# DAPule-LPC11U35-v1_2_0.net
KiCad netlist of a schematic drawn in EAGLE
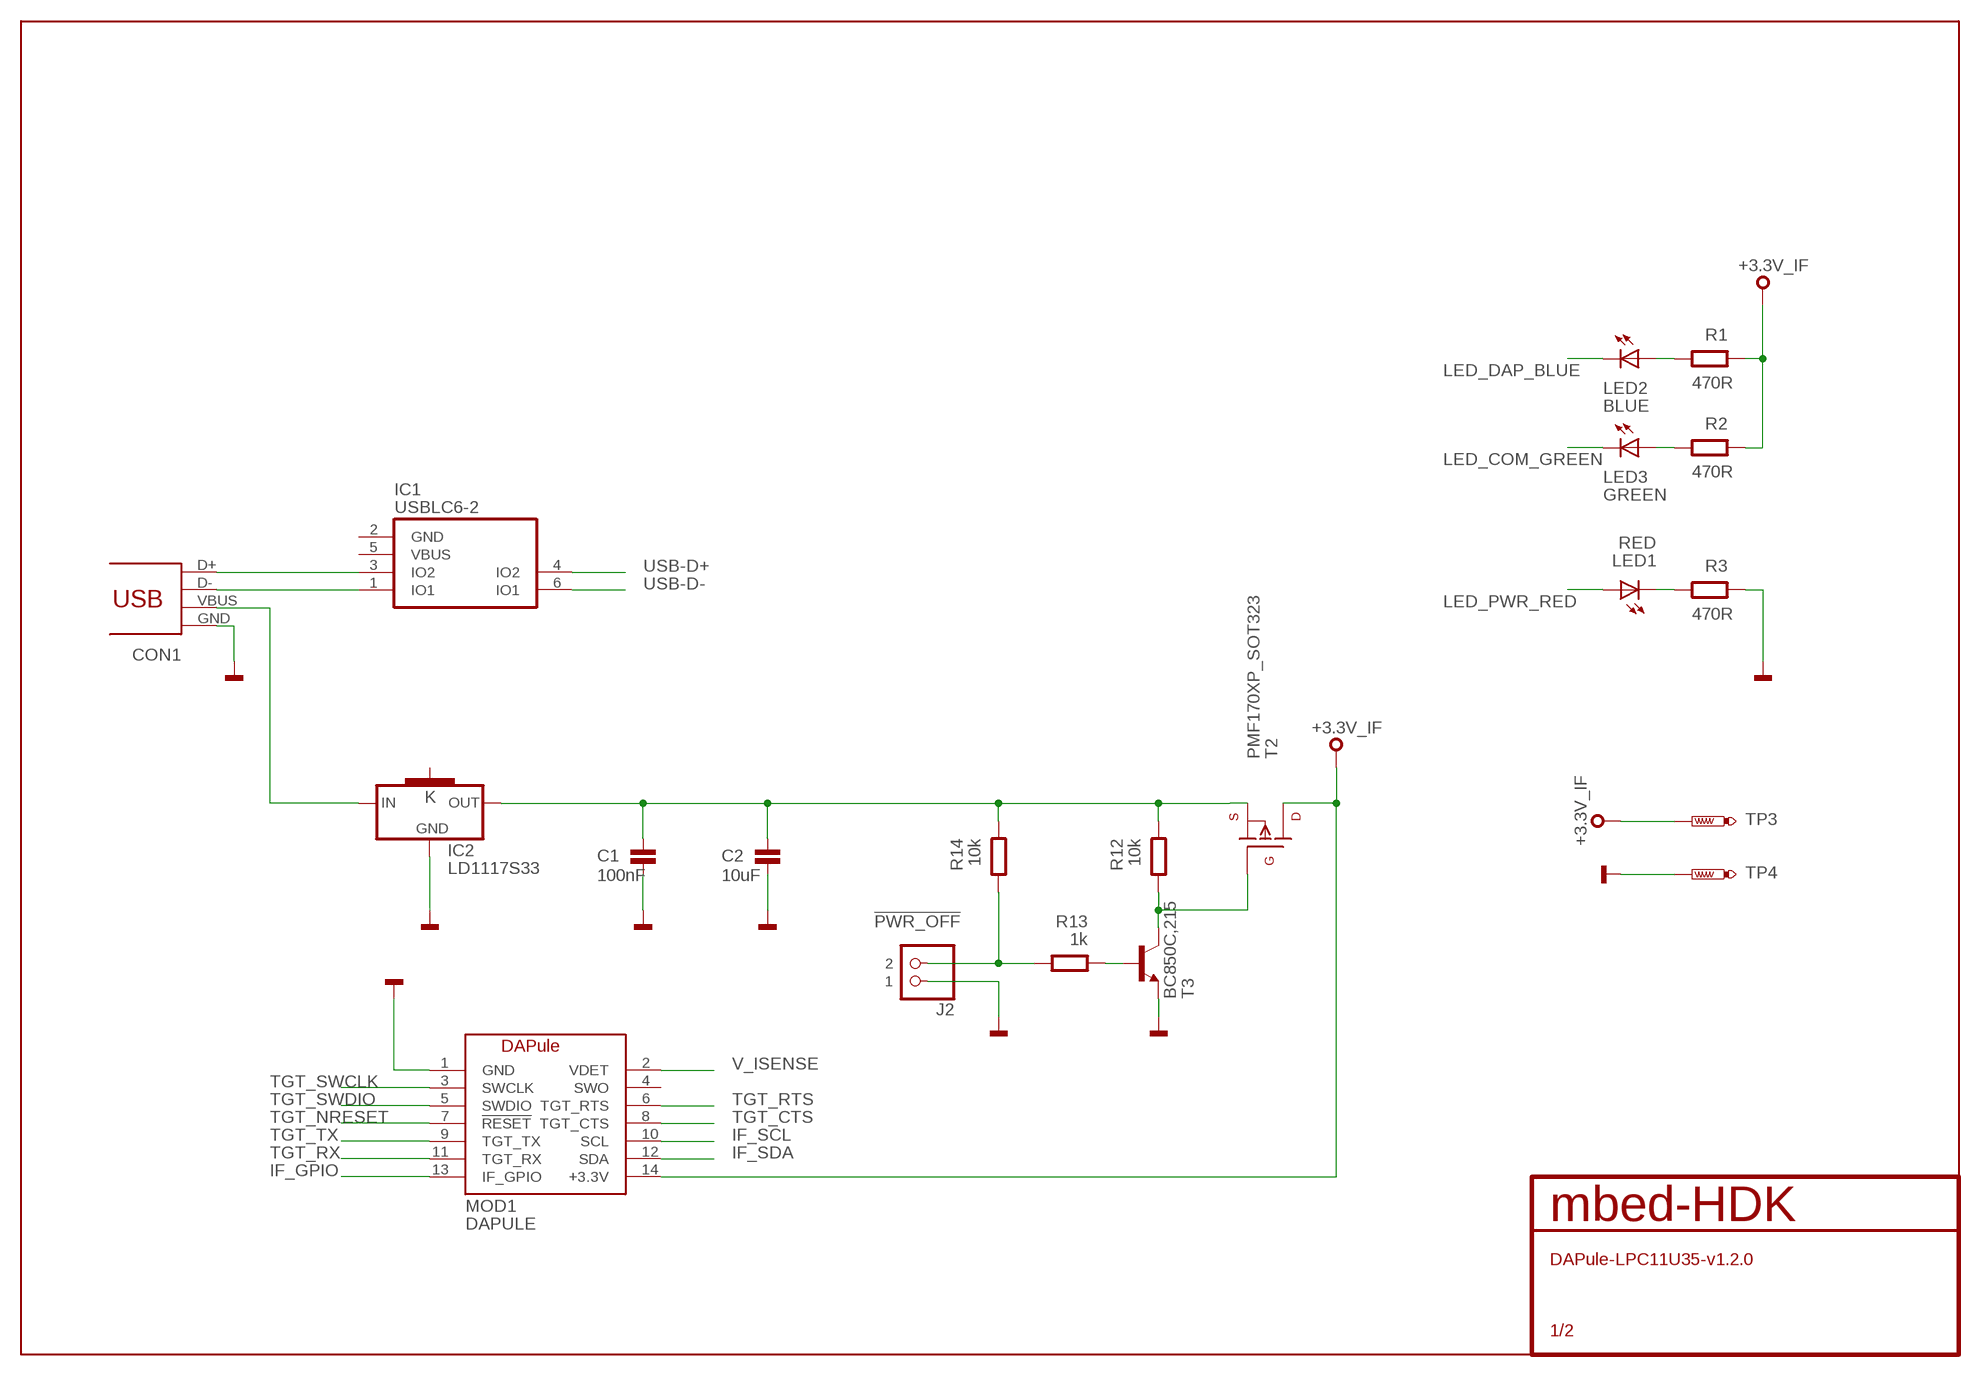
[diagram p0: schematic, sheet 1]
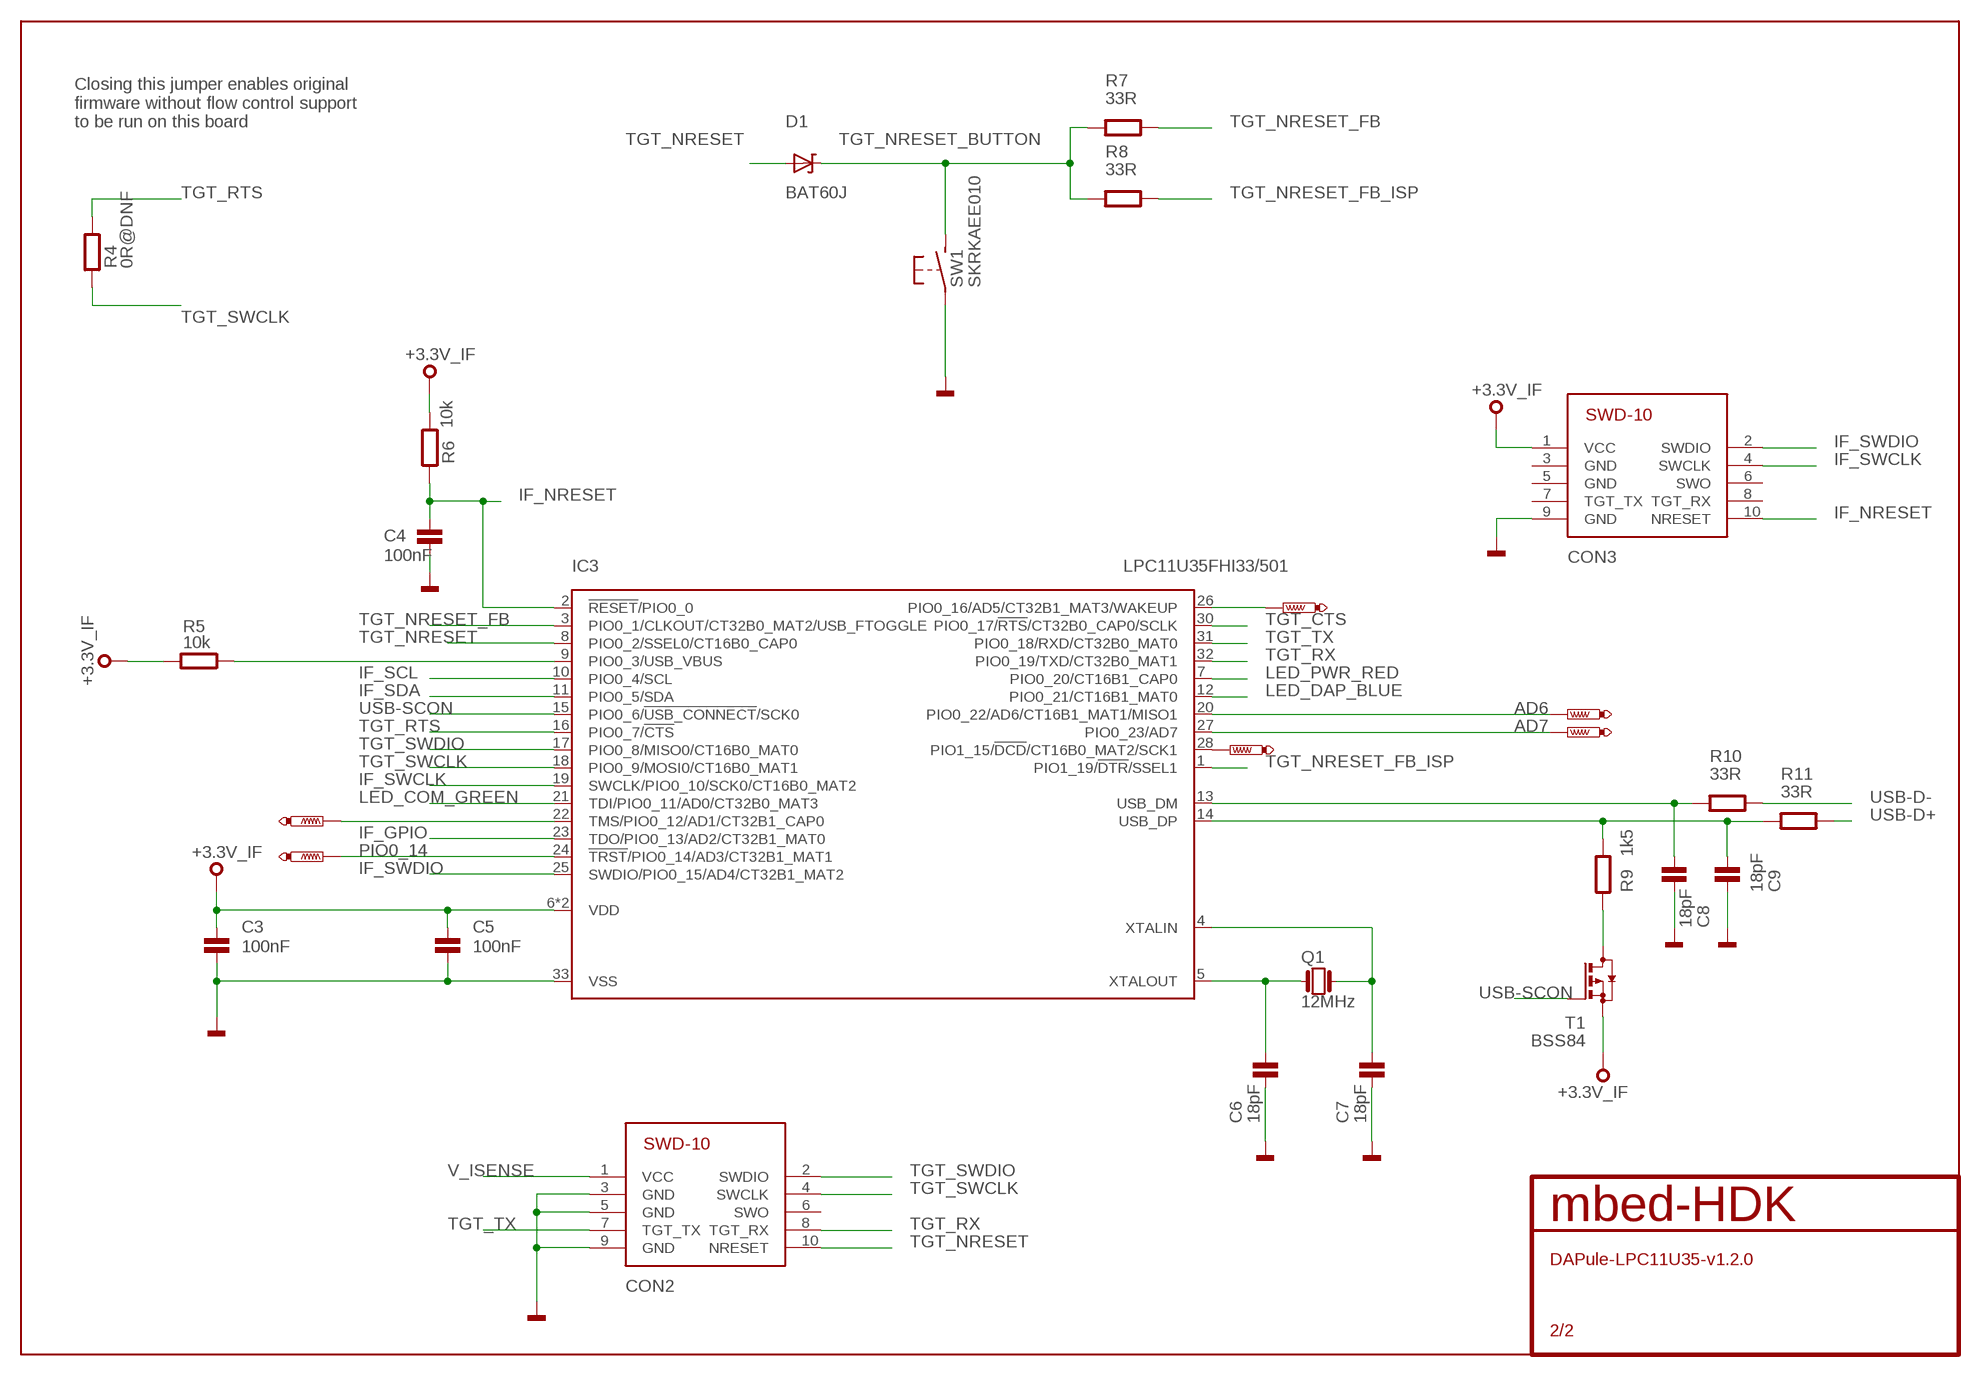
[diagram p1: schematic, sheet 2]

(export (version "E")
  (design (tool "Eeschema 10.0.6"))
  (components
    (comp (ref "C1")
      (value "100nF")
      (footprint "eagle-import:0603")
      (libsource (lib "eagle-import") (part "C0603"))
    )
    (comp (ref "C2")
      (value "10uF")
      (footprint "eagle-import:0603")
      (libsource (lib "eagle-import") (part "C0603"))
    )
    (comp (ref "CON1")
      (value "USB_MICROB")
      (footprint "eagle-import:MOLEX-47364-0001")
      (libsource (lib "eagle-import") (part "USB_MICROB"))
    )
    (comp (ref "IC1")
      (value "USBLC6-2SC6")
      (footprint "eagle-import:SOT23-6L")
      (libsource (lib "eagle-import") (part "USBLC6-2SC6"))
    )
    (comp (ref "IC2")
      (value "LD1117S33")
      (footprint "eagle-import:SOT223")
      (libsource (lib "eagle-import") (part "LD1117S33"))
    )
    (comp (ref "J2")
      (value "PINHD-1X2")
      (footprint "eagle-import:1X02")
      (fields (field (name "MF") "Wurth"))
      (libsource (lib "eagle-import") (part "PINHD-1X2"))
    )
    (comp (ref "LED1")
      (value "RED")
      (footprint "eagle-import:CHIPLED_0603")
      (libsource (lib "eagle-import") (part "LED0603"))
    )
    (comp (ref "LED2")
      (value "BLUE")
      (footprint "eagle-import:CHIPLED_0603")
      (libsource (lib "eagle-import") (part "LED0603"))
    )
    (comp (ref "LED3")
      (value "GREEN")
      (footprint "eagle-import:CHIPLED_0603")
      (libsource (lib "eagle-import") (part "LED0603"))
    )
    (comp (ref "MOD1")
      (value "DAPULE")
      (footprint "eagle-import:DAPULE")
      (libsource (lib "eagle-import") (part "DAPULE"))
    )
    (comp (ref "R1")
      (value "470R")
      (footprint "eagle-import:0603@1")
      (libsource (lib "eagle-import") (part "R0603"))
    )
    (comp (ref "R2")
      (value "470R")
      (footprint "eagle-import:0603@1")
      (libsource (lib "eagle-import") (part "R0603"))
    )
    (comp (ref "R3")
      (value "470R")
      (footprint "eagle-import:0603@1")
      (libsource (lib "eagle-import") (part "R0603"))
    )
    (comp (ref "R12")
      (value "10k")
      (footprint "eagle-import:0603@1")
      (libsource (lib "eagle-import") (part "R0603"))
    )
    (comp (ref "R13")
      (value "1k")
      (footprint "eagle-import:0603@1")
      (libsource (lib "eagle-import") (part "R0603"))
    )
    (comp (ref "R14")
      (value "10k")
      (footprint "eagle-import:0603@1")
      (libsource (lib "eagle-import") (part "R0603"))
    )
    (comp (ref "T2")
      (value "PMF170XP_SOT323")
      (footprint "eagle-import:SOT323-BEC")
      (fields (field (name "MF") "NEXPERIA"))
      (libsource (lib "eagle-import") (part "PMF170XP_SOT323"))
    )
    (comp (ref "T3")
      (value "BC850C,215")
      (footprint "eagle-import:SOT23-3")
      (fields (field (name "MF") "NXP Semiconductors"))
      (libsource (lib "eagle-import") (part "BC850C,215"))
    )
    (comp (ref "TP3")
      (value "TEST-POINT-50R-PTH")
      (footprint "eagle-import:TP50-PTH")
      (libsource (lib "eagle-import") (part "TEST-POINT-50R-PTH"))
    )
    (comp (ref "TP4")
      (value "TEST-POINT-50R-PTH")
      (footprint "eagle-import:TP50-PTH")
      (libsource (lib "eagle-import") (part "TEST-POINT-50R-PTH"))
    )
    (comp (ref "C3")
      (value "100nF")
      (footprint "eagle-import:0603")
      (libsource (lib "eagle-import") (part "C0603"))
    )
    (comp (ref "C4")
      (value "100nF")
      (footprint "eagle-import:0603")
      (libsource (lib "eagle-import") (part "C0603"))
    )
    (comp (ref "C5")
      (value "100nF")
      (footprint "eagle-import:0603")
      (libsource (lib "eagle-import") (part "C0603"))
    )
    (comp (ref "C6")
      (value "18pF")
      (footprint "eagle-import:0603")
      (libsource (lib "eagle-import") (part "C0603"))
    )
    (comp (ref "C7")
      (value "18pF")
      (footprint "eagle-import:0603")
      (libsource (lib "eagle-import") (part "C0603"))
    )
    (comp (ref "C8")
      (value "18pF")
      (footprint "eagle-import:0603")
      (libsource (lib "eagle-import") (part "C0603"))
    )
    (comp (ref "C9")
      (value "18pF")
      (footprint "eagle-import:0603")
      (libsource (lib "eagle-import") (part "C0603"))
    )
    (comp (ref "CON2")
      (value "SWD-10/TC2050_SMD")
      (footprint "eagle-import:FTSH-105-02")
      (libsource (lib "eagle-import") (part "SWD-10/TC2050_SMD"))
    )
    (comp (ref "CON3")
      (value "SWD-10/TC2050_SMD")
      (footprint "eagle-import:FTSH-105-02")
      (libsource (lib "eagle-import") (part "SWD-10/TC2050_SMD"))
    )
    (comp (ref "D1")
      (value "BAT60J")
      (footprint "eagle-import:SOD323")
      (fields (field (name "MF") "STMicroelectronics"))
      (libsource (lib "eagle-import") (part "BAT60J"))
    )
    (comp (ref "IC3")
      (value "LPC11U35FHI33/501")
      (footprint "eagle-import:SOT617-3")
      (libsource (lib "eagle-import") (part "LPC11U35FHI33/501"))
    )
    (comp (ref "Q1")
      (value "12MHz")
      (footprint "eagle-import:3.2X.2.5")
      (libsource (lib "eagle-import") (part "Q_3.2X2.5"))
    )
    (comp (ref "R4")
      (value "0R@DNF")
      (footprint "eagle-import:0402@1")
      (libsource (lib "eagle-import") (part "R0402"))
    )
    (comp (ref "R5")
      (value "10k")
      (footprint "eagle-import:0603@1")
      (libsource (lib "eagle-import") (part "R0603"))
    )
    (comp (ref "R6")
      (value "10k")
      (footprint "eagle-import:0603@1")
      (libsource (lib "eagle-import") (part "R0603"))
    )
    (comp (ref "R7")
      (value "33R")
      (footprint "eagle-import:0603@1")
      (libsource (lib "eagle-import") (part "R0603"))
    )
    (comp (ref "R8")
      (value "33R")
      (footprint "eagle-import:0603@1")
      (libsource (lib "eagle-import") (part "R0603"))
    )
    (comp (ref "R9")
      (value "1k5")
      (footprint "eagle-import:0603@1")
      (libsource (lib "eagle-import") (part "R0603"))
    )
    (comp (ref "R10")
      (value "33R")
      (footprint "eagle-import:0603@1")
      (libsource (lib "eagle-import") (part "R0603"))
    )
    (comp (ref "R11")
      (value "33R")
      (footprint "eagle-import:0603@1")
      (libsource (lib "eagle-import") (part "R0603"))
    )
    (comp (ref "SW1")
      (value "SKRKAEE010")
      (footprint "eagle-import:SKRKAEE010")
      (fields (field (name "MF") "ALPS"))
      (libsource (lib "eagle-import") (part "SKRKAEE010"))
    )
    (comp (ref "T1")
      (value "BSS84")
      (footprint "eagle-import:SOT23")
      (libsource (lib "eagle-import") (part "BSS84"))
    )
    (comp (ref "TP1")
      (value "PTR1TP07R")
      (footprint "eagle-import:TP07R")
      (libsource (lib "eagle-import") (part "PTR1TP07R"))
    )
    (comp (ref "TP2")
      (value "PTR1TP07R")
      (footprint "eagle-import:TP07R")
      (libsource (lib "eagle-import") (part "PTR1TP07R"))
    )
    (comp (ref "TP5")
      (value "PTR1TP07R")
      (footprint "eagle-import:TP07R")
      (libsource (lib "eagle-import") (part "PTR1TP07R"))
    )
    (comp (ref "TP8")
      (value "PTR1TP07R")
      (footprint "eagle-import:TP07R")
      (libsource (lib "eagle-import") (part "PTR1TP07R"))
    )
    (comp (ref "TP9")
      (value "PTR1TP07R")
      (footprint "eagle-import:TP07R")
      (libsource (lib "eagle-import") (part "PTR1TP07R"))
    )
    (comp (ref "TP13")
      (value "PTR1TP07R")
      (footprint "eagle-import:TP07R")
      (libsource (lib "eagle-import") (part "PTR1TP07R"))
    )
  )
  (nets
    (net (code "1") (name "+3.3V_IF") (class "Default")
      (node (ref "C3") (pin "1") (pinfunction "P$1_1") (pintype "passive"))
      (node (ref "C5") (pin "1") (pinfunction "P$1_1") (pintype "passive"))
      (node (ref "CON3") (pin "1") (pinfunction "VCC_1") (pintype "bidirectional"))
      (node (ref "IC3") (pin "29") (pinfunction "VDD_29") (pintype "passive"))
      (node (ref "IC3") (pin "6") (pinfunction "VDD_6") (pintype "passive"))
      (node (ref "MOD1") (pin "14") (pinfunction "+3.3V_14") (pintype "bidirectional"))
      (node (ref "R1") (pin "1") (pinfunction "P$1_1") (pintype "passive"))
      (node (ref "R2") (pin "1") (pinfunction "P$1_1") (pintype "passive"))
      (node (ref "R5") (pin "2") (pinfunction "P$2_2") (pintype "passive"))
      (node (ref "R6") (pin "2") (pinfunction "P$2_2") (pintype "passive"))
      (node (ref "T1") (pin "2") (pinfunction "S_2") (pintype "passive"))
      (node (ref "T2") (pin "C") (pinfunction "D_C") (pintype "passive"))
      (node (ref "TP3") (pin "TP") (pinfunction "TP_TP") (pintype "input"))
    )
    (net (code "2") (name "AD6") (class "Default")
      (node (ref "IC3") (pin "20") (pinfunction "PIO0_22/AD6/CT16B1_MAT1/MISO1_20") (pintype "bidirectional"))
      (node (ref "TP9") (pin "TP") (pinfunction "TP_TP") (pintype "input"))
    )
    (net (code "3") (name "AD7") (class "Default")
      (node (ref "IC3") (pin "27") (pinfunction "PIO0_23/AD7_27") (pintype "bidirectional"))
      (node (ref "TP8") (pin "TP") (pinfunction "TP_TP") (pintype "input"))
    )
    (net (code "4") (name "GND") (class "Default")
      (node (ref "C1") (pin "2") (pinfunction "P$2_2") (pintype "passive"))
      (node (ref "C2") (pin "2") (pinfunction "P$2_2") (pintype "passive"))
      (node (ref "C3") (pin "2") (pinfunction "P$2_2") (pintype "passive"))
      (node (ref "C4") (pin "2") (pinfunction "P$2_2") (pintype "passive"))
      (node (ref "C5") (pin "2") (pinfunction "P$2_2") (pintype "passive"))
      (node (ref "C6") (pin "2") (pinfunction "P$2_2") (pintype "passive"))
      (node (ref "C7") (pin "2") (pinfunction "P$2_2") (pintype "passive"))
      (node (ref "C8") (pin "2") (pinfunction "P$2_2") (pintype "passive"))
      (node (ref "C9") (pin "2") (pinfunction "P$2_2") (pintype "passive"))
      (node (ref "CON1") (pin "GND") (pinfunction "GND_GND") (pintype "bidirectional"))
      (node (ref "CON2") (pin "3") (pinfunction "GND_3") (pintype "bidirectional"))
      (node (ref "CON2") (pin "5") (pinfunction "GND_5") (pintype "bidirectional"))
      (node (ref "CON2") (pin "9") (pinfunction "GND_9") (pintype "bidirectional"))
      (node (ref "CON3") (pin "9") (pinfunction "GND_9") (pintype "bidirectional"))
      (node (ref "IC2") (pin "1") (pinfunction "GND_1") (pintype "input"))
      (node (ref "IC3") (pin "33") (pinfunction "VSS_33") (pintype "passive"))
      (node (ref "J2") (pin "1") (pinfunction "1_1") (pintype "passive"))
      (node (ref "MOD1") (pin "1") (pinfunction "GND_1") (pintype "bidirectional"))
      (node (ref "R3") (pin "1") (pinfunction "P$1_1") (pintype "passive"))
      (node (ref "SW1") (pin "P$1") (pinfunction "P_P$1") (pintype "passive"))
      (node (ref "T3") (pin "2") (pinfunction "E_2") (pintype "passive"))
      (node (ref "TP4") (pin "TP") (pinfunction "TP_TP") (pintype "input"))
    )
    (net (code "5") (name "IF_GPIO") (class "Default")
      (node (ref "IC3") (pin "23") (pinfunction "TDO/PIO0_13/AD2/CT32B1_MAT0_23") (pintype "bidirectional"))
      (node (ref "MOD1") (pin "13") (pinfunction "IF_GPIO_13") (pintype "bidirectional"))
    )
    (net (code "6") (name "IF_NRESET") (class "Default")
      (node (ref "C4") (pin "1") (pinfunction "P$1_1") (pintype "passive"))
      (node (ref "CON3") (pin "10") (pinfunction "NRESET_10") (pintype "bidirectional"))
      (node (ref "IC3") (pin "2") (pinfunction "~{RESET}/PIO0_0_2") (pintype "bidirectional"))
      (node (ref "R6") (pin "1") (pinfunction "P$1_1") (pintype "passive"))
    )
    (net (code "7") (name "IF_SCL") (class "Default")
      (node (ref "IC3") (pin "10") (pinfunction "PIO0_4/SCL_10") (pintype "bidirectional"))
      (node (ref "MOD1") (pin "10") (pinfunction "SCL_10") (pintype "bidirectional"))
    )
    (net (code "8") (name "IF_SDA") (class "Default")
      (node (ref "IC3") (pin "11") (pinfunction "PIO0_5/SDA_11") (pintype "bidirectional"))
      (node (ref "MOD1") (pin "12") (pinfunction "SDA_12") (pintype "bidirectional"))
    )
    (net (code "9") (name "IF_SWCLK") (class "Default")
      (node (ref "CON3") (pin "4") (pinfunction "SWCLK_4") (pintype "bidirectional"))
      (node (ref "IC3") (pin "19") (pinfunction "SWCLK/PIO0_10/SCK0/CT16B0_MAT2_19") (pintype "bidirectional"))
    )
    (net (code "10") (name "IF_SWDIO") (class "Default")
      (node (ref "CON3") (pin "2") (pinfunction "SWDIO_2") (pintype "bidirectional"))
      (node (ref "IC3") (pin "25") (pinfunction "SWDIO/PIO0_15/AD4/CT32B1_MAT2_25") (pintype "bidirectional"))
    )
    (net (code "11") (name "LED_COM_GREEN") (class "Default")
      (node (ref "IC3") (pin "21") (pinfunction "TDI/PIO0_11/AD0/CT32B0_MAT3_21") (pintype "bidirectional"))
      (node (ref "LED3") (pin "C") (pinfunction "C_C") (pintype "passive"))
    )
    (net (code "12") (name "LED_DAP_BLUE") (class "Default")
      (node (ref "IC3") (pin "12") (pinfunction "PIO0_21/CT16B1_MAT0_12") (pintype "bidirectional"))
      (node (ref "LED2") (pin "C") (pinfunction "C_C") (pintype "passive"))
    )
    (net (code "13") (name "LED_PWR_RED") (class "Default")
      (node (ref "IC3") (pin "7") (pinfunction "PIO0_20/CT16B1_CAP0_7") (pintype "bidirectional"))
      (node (ref "LED1") (pin "A") (pinfunction "A_A") (pintype "passive"))
    )
    (net (code "14") (name "Net-(C1-P$1)") (class "Default")
      (node (ref "C1") (pin "1") (pinfunction "P$1_1") (pintype "passive"))
      (node (ref "C2") (pin "1") (pinfunction "P$1_1") (pintype "passive"))
      (node (ref "IC2") (pin "2") (pinfunction "OUT_2") (pintype "passive"))
      (node (ref "R12") (pin "1") (pinfunction "P$1_1") (pintype "passive"))
      (node (ref "R14") (pin "1") (pinfunction "P$1_1") (pintype "passive"))
      (node (ref "T2") (pin "E") (pinfunction "S_E") (pintype "passive"))
    )
    (net (code "15") (name "Net-(C6-P$1)") (class "Default")
      (node (ref "C6") (pin "1") (pinfunction "P$1_1") (pintype "passive"))
      (node (ref "IC3") (pin "5") (pinfunction "XTALOUT_5") (pintype "output"))
      (node (ref "Q1") (pin "P$1") (pinfunction "1_P$1") (pintype "passive"))
    )
    (net (code "16") (name "Net-(C7-P$1)") (class "Default")
      (node (ref "C7") (pin "1") (pinfunction "P$1_1") (pintype "passive"))
      (node (ref "IC3") (pin "4") (pinfunction "XTALIN_4") (pintype "input"))
      (node (ref "Q1") (pin "P$3") (pinfunction "2_P$3") (pintype "passive"))
    )
    (net (code "17") (name "Net-(C8-P$1)") (class "Default")
      (node (ref "C8") (pin "1") (pinfunction "P$1_1") (pintype "passive"))
      (node (ref "IC3") (pin "13") (pinfunction "USB_DM_13") (pintype "bidirectional"))
      (node (ref "R10") (pin "2") (pinfunction "P$2_2") (pintype "passive"))
    )
    (net (code "18") (name "Net-(C9-P$1)") (class "Default")
      (node (ref "C9") (pin "1") (pinfunction "P$1_1") (pintype "passive"))
      (node (ref "IC3") (pin "14") (pinfunction "USB_DP_14") (pintype "bidirectional"))
      (node (ref "R11") (pin "2") (pinfunction "P$2_2") (pintype "passive"))
      (node (ref "R9") (pin "2") (pinfunction "P$2_2") (pintype "passive"))
    )
    (net (code "19") (name "Net-(CON1-PadD+)") (class "Default")
      (node (ref "CON1") (pin "D+") (pinfunction "D+_D+") (pintype "bidirectional"))
      (node (ref "IC1") (pin "3") (pinfunction "IO2_3") (pintype "bidirectional"))
    )
    (net (code "20") (name "Net-(CON1-PadD-)") (class "Default")
      (node (ref "CON1") (pin "D-") (pinfunction "D-_D-") (pintype "bidirectional"))
      (node (ref "IC1") (pin "1") (pinfunction "IO1_1") (pintype "bidirectional"))
    )
    (net (code "21") (name "Net-(IC2-IN)") (class "Default")
      (node (ref "CON1") (pin "VBUS") (pinfunction "VBUS_VBUS") (pintype "bidirectional"))
      (node (ref "IC2") (pin "3") (pinfunction "IN_3") (pintype "input"))
    )
    (net (code "22") (name "Net-(IC3-PIO0_3{slash}USB_VBUS)") (class "Default")
      (node (ref "IC3") (pin "9") (pinfunction "PIO0_3/USB_VBUS_9") (pintype "bidirectional"))
      (node (ref "R5") (pin "1") (pinfunction "P$1_1") (pintype "passive"))
    )
    (net (code "23") (name "Net-(IC3-PIO0_16{slash}AD5{slash}CT32B1_MAT3{slash}WAKEUP)") (class "Default")
      (node (ref "IC3") (pin "26") (pinfunction "PIO0_16/AD5/CT32B1_MAT3/WAKEUP_26") (pintype "bidirectional"))
      (node (ref "TP2") (pin "TP") (pinfunction "TP_TP") (pintype "input"))
    )
    (net (code "24") (name "Net-(IC3-PIO1_15{slash}~{DCD}{slash}CT16B0_MAT2{slash}SCK1)") (class "Default")
      (node (ref "IC3") (pin "28") (pinfunction "PIO1_15/~{DCD}/CT16B0_MAT2/SCK1_28") (pintype "bidirectional"))
      (node (ref "TP5") (pin "TP") (pinfunction "TP_TP") (pintype "input"))
    )
    (net (code "25") (name "Net-(IC3-TMS{slash}PIO0_12{slash}AD1{slash}CT32B1_CAP0)") (class "Default")
      (node (ref "IC3") (pin "22") (pinfunction "TMS/PIO0_12/AD1/CT32B1_CAP0_22") (pintype "bidirectional"))
      (node (ref "TP1") (pin "TP") (pinfunction "TP_TP") (pintype "input"))
    )
    (net (code "26") (name "Net-(R1-P$2)") (class "Default")
      (node (ref "LED2") (pin "A") (pinfunction "A_A") (pintype "passive"))
      (node (ref "R1") (pin "2") (pinfunction "P$2_2") (pintype "passive"))
    )
    (net (code "27") (name "Net-(R2-P$2)") (class "Default")
      (node (ref "LED3") (pin "A") (pinfunction "A_A") (pintype "passive"))
      (node (ref "R2") (pin "2") (pinfunction "P$2_2") (pintype "passive"))
    )
    (net (code "28") (name "Net-(R3-P$2)") (class "Default")
      (node (ref "LED1") (pin "C") (pinfunction "C_C") (pintype "passive"))
      (node (ref "R3") (pin "2") (pinfunction "P$2_2") (pintype "passive"))
    )
    (net (code "29") (name "Net-(R9-P$1)") (class "Default")
      (node (ref "R9") (pin "1") (pinfunction "P$1_1") (pintype "passive"))
      (node (ref "T1") (pin "3") (pinfunction "D_3") (pintype "passive"))
    )
    (net (code "30") (name "Net-(R12-P$2)") (class "Default")
      (node (ref "R12") (pin "2") (pinfunction "P$2_2") (pintype "passive"))
      (node (ref "T2") (pin "B") (pinfunction "G_B") (pintype "passive"))
      (node (ref "T3") (pin "3") (pinfunction "C_3") (pintype "passive"))
    )
    (net (code "31") (name "Net-(R13-P$1)") (class "Default")
      (node (ref "R13") (pin "1") (pinfunction "P$1_1") (pintype "passive"))
      (node (ref "T3") (pin "1") (pinfunction "B_1") (pintype "passive"))
    )
    (net (code "32") (name "PIO0_14") (class "Default")
      (node (ref "IC3") (pin "24") (pinfunction "~{TRST}/PIO0_14/AD3/CT32B1_MAT1_24") (pintype "bidirectional"))
      (node (ref "TP13") (pin "TP") (pinfunction "TP_TP") (pintype "input"))
    )
    (net (code "33") (name "TGT_CTS") (class "Default")
      (node (ref "IC3") (pin "30") (pinfunction "PIO0_17/~{RTS}/CT32B0_CAP0/SCLK_30") (pintype "bidirectional"))
      (node (ref "MOD1") (pin "8") (pinfunction "TGT_CTS_8") (pintype "bidirectional"))
    )
    (net (code "34") (name "TGT_NRESET") (class "Default")
      (node (ref "CON2") (pin "10") (pinfunction "NRESET_10") (pintype "bidirectional"))
      (node (ref "D1") (pin "A") (pinfunction "A_A") (pintype "passive"))
      (node (ref "IC3") (pin "8") (pinfunction "PIO0_2/SSEL0/CT16B0_CAP0_8") (pintype "bidirectional"))
      (node (ref "MOD1") (pin "7") (pinfunction "~{RESET}_7") (pintype "bidirectional"))
    )
    (net (code "35") (name "TGT_NRESET_BUTTON") (class "Default")
      (node (ref "D1") (pin "K") (pinfunction "K_K") (pintype "passive"))
      (node (ref "R7") (pin "2") (pinfunction "P$2_2") (pintype "passive"))
      (node (ref "R8") (pin "2") (pinfunction "P$2_2") (pintype "passive"))
      (node (ref "SW1") (pin "P$2") (pinfunction "S_P$2") (pintype "passive"))
    )
    (net (code "36") (name "TGT_NRESET_FB") (class "Default")
      (node (ref "IC3") (pin "3") (pinfunction "PIO0_1/CLKOUT/CT32B0_MAT2/USB_FTOGGLE_3") (pintype "bidirectional"))
      (node (ref "R7") (pin "1") (pinfunction "P$1_1") (pintype "passive"))
    )
    (net (code "37") (name "TGT_NRESET_FB_ISP") (class "Default")
      (node (ref "IC3") (pin "1") (pinfunction "PIO1_19/~{DTR}/SSEL1_1") (pintype "bidirectional"))
      (node (ref "R8") (pin "1") (pinfunction "P$1_1") (pintype "passive"))
    )
    (net (code "38") (name "TGT_RTS") (class "Default")
      (node (ref "IC3") (pin "16") (pinfunction "PIO0_7/~{CTS}_16") (pintype "bidirectional"))
      (node (ref "MOD1") (pin "6") (pinfunction "TGT_RTS_6") (pintype "bidirectional"))
      (node (ref "R4") (pin "2") (pinfunction "P$2_2") (pintype "passive"))
    )
    (net (code "39") (name "TGT_RX") (class "Default")
      (node (ref "CON2") (pin "8") (pinfunction "TGT_RX_8") (pintype "bidirectional"))
      (node (ref "IC3") (pin "32") (pinfunction "PIO0_19/TXD/CT32B0_MAT1_32") (pintype "bidirectional"))
      (node (ref "MOD1") (pin "11") (pinfunction "TGT_RX_11") (pintype "bidirectional"))
    )
    (net (code "40") (name "TGT_SWCLK") (class "Default")
      (node (ref "CON2") (pin "4") (pinfunction "SWCLK_4") (pintype "bidirectional"))
      (node (ref "IC3") (pin "18") (pinfunction "PIO0_9/MOSI0/CT16B0_MAT1_18") (pintype "bidirectional"))
      (node (ref "MOD1") (pin "3") (pinfunction "SWCLK_3") (pintype "bidirectional"))
      (node (ref "R4") (pin "1") (pinfunction "P$1_1") (pintype "passive"))
    )
    (net (code "41") (name "TGT_SWDIO") (class "Default")
      (node (ref "CON2") (pin "2") (pinfunction "SWDIO_2") (pintype "bidirectional"))
      (node (ref "IC3") (pin "17") (pinfunction "PIO0_8/MISO0/CT16B0_MAT0_17") (pintype "bidirectional"))
      (node (ref "MOD1") (pin "5") (pinfunction "SWDIO_5") (pintype "bidirectional"))
    )
    (net (code "42") (name "TGT_TX") (class "Default")
      (node (ref "CON2") (pin "7") (pinfunction "TGT_TX_7") (pintype "bidirectional"))
      (node (ref "IC3") (pin "31") (pinfunction "PIO0_18/RXD/CT32B0_MAT0_31") (pintype "bidirectional"))
      (node (ref "MOD1") (pin "9") (pinfunction "TGT_TX_9") (pintype "bidirectional"))
    )
    (net (code "43") (name "USB-D+") (class "Default")
      (node (ref "IC1") (pin "4") (pinfunction "IO2_4") (pintype "bidirectional"))
      (node (ref "R11") (pin "1") (pinfunction "P$1_1") (pintype "passive"))
    )
    (net (code "44") (name "USB-D-") (class "Default")
      (node (ref "IC1") (pin "6") (pinfunction "IO1_6") (pintype "bidirectional"))
      (node (ref "R10") (pin "1") (pinfunction "P$1_1") (pintype "passive"))
    )
    (net (code "45") (name "USB-SCON") (class "Default")
      (node (ref "IC3") (pin "15") (pinfunction "PIO0_6/~{USB_CONNECT}/SCK0_15") (pintype "bidirectional"))
      (node (ref "T1") (pin "1") (pinfunction "G_1") (pintype "passive"))
    )
    (net (code "46") (name "V_ISENSE") (class "Default")
      (node (ref "CON2") (pin "1") (pinfunction "VCC_1") (pintype "bidirectional"))
      (node (ref "MOD1") (pin "2") (pinfunction "VDET_2") (pintype "bidirectional"))
    )
    (net (code "47") (name "unconnected-(CON2-SWO-Pad6)") (class "Default")
      (node (ref "CON2") (pin "6") (pinfunction "SWO_6") (pintype "bidirectional"))
    )
    (net (code "48") (name "unconnected-(CON3-GND-Pad3)") (class "Default")
      (node (ref "CON3") (pin "3") (pinfunction "GND_3") (pintype "bidirectional"))
    )
    (net (code "49") (name "unconnected-(CON3-GND-Pad5)") (class "Default")
      (node (ref "CON3") (pin "5") (pinfunction "GND_5") (pintype "bidirectional"))
    )
    (net (code "50") (name "unconnected-(CON3-SWO-Pad6)") (class "Default")
      (node (ref "CON3") (pin "6") (pinfunction "SWO_6") (pintype "bidirectional"))
    )
    (net (code "51") (name "unconnected-(CON3-TGT_RX-Pad8)") (class "Default")
      (node (ref "CON3") (pin "8") (pinfunction "TGT_RX_8") (pintype "bidirectional"))
    )
    (net (code "52") (name "unconnected-(CON3-TGT_TX-Pad7)") (class "Default")
      (node (ref "CON3") (pin "7") (pinfunction "TGT_TX_7") (pintype "bidirectional"))
    )
    (net (code "53") (name "unconnected-(IC1-GND-Pad2)") (class "Default")
      (node (ref "IC1") (pin "2") (pinfunction "GND_2") (pintype "bidirectional"))
    )
    (net (code "54") (name "unconnected-(IC1-VBUS-Pad5)") (class "Default")
      (node (ref "IC1") (pin "5") (pinfunction "VBUS_5") (pintype "bidirectional"))
    )
    (net (code "55") (name "unconnected-(IC2-K-Pad4)") (class "Default")
      (node (ref "IC2") (pin "4") (pinfunction "K_4") (pintype "passive"))
    )
    (net (code "56") (name "unconnected-(MOD1-SWO-Pad4)") (class "Default")
      (node (ref "MOD1") (pin "4") (pinfunction "SWO_4") (pintype "bidirectional"))
    )
    (net (code "57") (name "~{PWR_OFF}") (class "Default")
      (node (ref "J2") (pin "2") (pinfunction "2_2") (pintype "passive"))
      (node (ref "R13") (pin "2") (pinfunction "P$2_2") (pintype "passive"))
      (node (ref "R14") (pin "2") (pinfunction "P$2_2") (pintype "passive"))
    )
  )
)
